# ProPrj__v1_0_2025-02-24.net
KiCad netlist of a schematic drawn in EasyEDA Pro
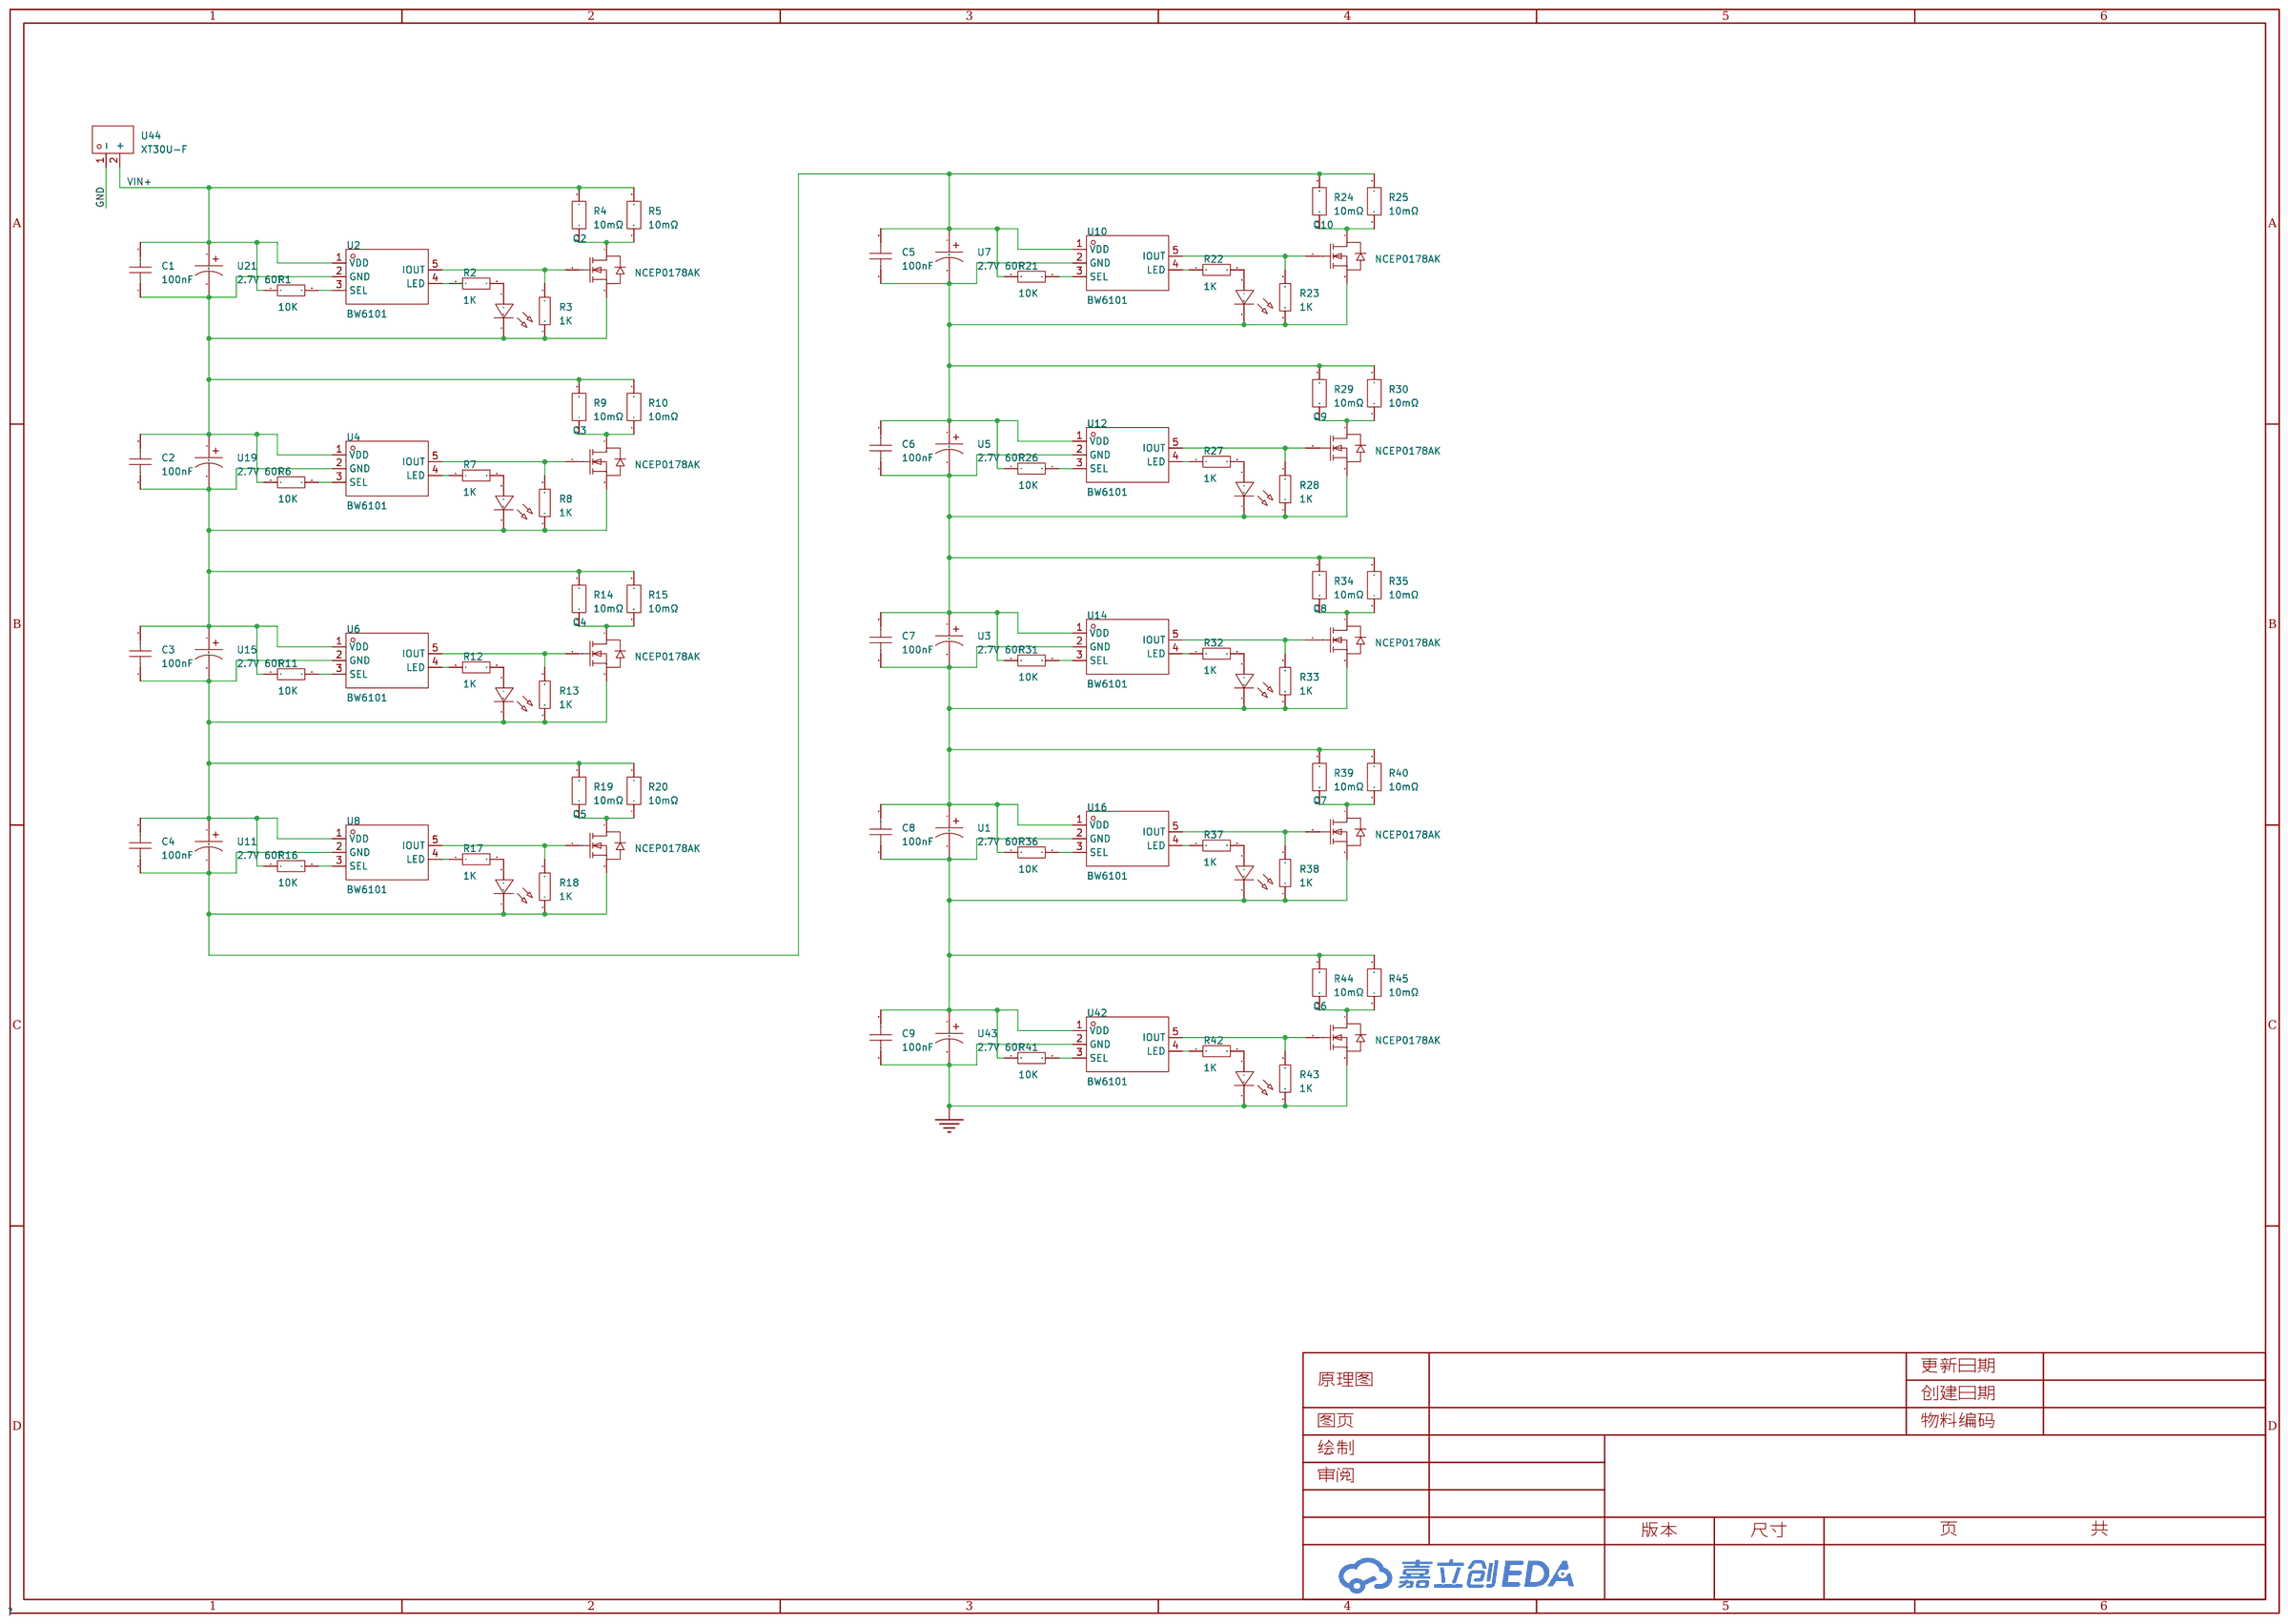
[diagram p0: schematic sheet]

(export (version "E")
  (design (tool "Eeschema 10.0.6"))
  (components
    (comp (ref "C1")
      (value "100nF")
      (footprint "easyedapro:C0805")
      (libsource (lib "easyedapro") (part "CapAcitance"))
    )
    (comp (ref "C2")
      (value "100nF")
      (footprint "easyedapro:C0805")
      (libsource (lib "easyedapro") (part "CapAcitance"))
    )
    (comp (ref "C3")
      (value "100nF")
      (footprint "easyedapro:C0805")
      (libsource (lib "easyedapro") (part "CapAcitance"))
    )
    (comp (ref "C4")
      (value "100nF")
      (footprint "easyedapro:C0805")
      (libsource (lib "easyedapro") (part "CapAcitance"))
    )
    (comp (ref "C5")
      (value "100nF")
      (footprint "easyedapro:C0805")
      (libsource (lib "easyedapro") (part "CapAcitance"))
    )
    (comp (ref "C6")
      (value "100nF")
      (footprint "easyedapro:C0805")
      (libsource (lib "easyedapro") (part "CapAcitance"))
    )
    (comp (ref "C7")
      (value "100nF")
      (footprint "easyedapro:C0805")
      (libsource (lib "easyedapro") (part "CapAcitance"))
    )
    (comp (ref "C8")
      (value "100nF")
      (footprint "easyedapro:C0805")
      (libsource (lib "easyedapro") (part "CapAcitance"))
    )
    (comp (ref "C9")
      (value "100nF")
      (footprint "easyedapro:C0805")
      (libsource (lib "easyedapro") (part "CapAcitance"))
    )
    (comp (ref "LED1")
      (value "~")
      (footprint "easyedapro:LED_0603")
      (libsource (lib "easyedapro") (part "LED_R"))
    )
    (comp (ref "LED2")
      (value "~")
      (footprint "easyedapro:LED_0603")
      (libsource (lib "easyedapro") (part "LED_R"))
    )
    (comp (ref "LED3")
      (value "~")
      (footprint "easyedapro:LED_0603")
      (libsource (lib "easyedapro") (part "LED_R"))
    )
    (comp (ref "LED4")
      (value "~")
      (footprint "easyedapro:LED_0603")
      (libsource (lib "easyedapro") (part "LED_R"))
    )
    (comp (ref "LED5")
      (value "~")
      (footprint "easyedapro:LED_0603")
      (libsource (lib "easyedapro") (part "LED_R"))
    )
    (comp (ref "LED6")
      (value "~")
      (footprint "easyedapro:LED_0603")
      (libsource (lib "easyedapro") (part "LED_R"))
    )
    (comp (ref "LED7")
      (value "~")
      (footprint "easyedapro:LED_0603")
      (libsource (lib "easyedapro") (part "LED_R"))
    )
    (comp (ref "LED8")
      (value "~")
      (footprint "easyedapro:LED_0603")
      (libsource (lib "easyedapro") (part "LED_R"))
    )
    (comp (ref "LED9")
      (value "~")
      (footprint "easyedapro:LED_0603")
      (libsource (lib "easyedapro") (part "LED_R"))
    )
    (comp (ref "Q2")
      (value "NCEP0178AK")
      (footprint "easyedapro:TO-252-2_L6.5-W6.1-P4.58-LS10.0-TL")
      (fields (field (name "Manufacturer") "NCE(无锡新洁能)"))
      (libsource (lib "easyedapro") (part "NCEP0178AK"))
    )
    (comp (ref "Q3")
      (value "NCEP0178AK")
      (footprint "easyedapro:TO-252-2_L6.5-W6.1-P4.58-LS10.0-TL")
      (fields (field (name "Manufacturer") "NCE(无锡新洁能)"))
      (libsource (lib "easyedapro") (part "NCEP0178AK"))
    )
    (comp (ref "Q4")
      (value "NCEP0178AK")
      (footprint "easyedapro:TO-252-2_L6.5-W6.1-P4.58-LS10.0-TL")
      (fields (field (name "Manufacturer") "NCE(无锡新洁能)"))
      (libsource (lib "easyedapro") (part "NCEP0178AK"))
    )
    (comp (ref "Q5")
      (value "NCEP0178AK")
      (footprint "easyedapro:TO-252-2_L6.5-W6.1-P4.58-LS10.0-TL")
      (fields (field (name "Manufacturer") "NCE(无锡新洁能)"))
      (libsource (lib "easyedapro") (part "NCEP0178AK"))
    )
    (comp (ref "Q6")
      (value "NCEP0178AK")
      (footprint "easyedapro:TO-252-2_L6.5-W6.1-P4.58-LS10.0-TL")
      (fields (field (name "Manufacturer") "NCE(无锡新洁能)"))
      (libsource (lib "easyedapro") (part "NCEP0178AK"))
    )
    (comp (ref "Q7")
      (value "NCEP0178AK")
      (footprint "easyedapro:TO-252-2_L6.5-W6.1-P4.58-LS10.0-TL")
      (fields (field (name "Manufacturer") "NCE(无锡新洁能)"))
      (libsource (lib "easyedapro") (part "NCEP0178AK"))
    )
    (comp (ref "Q8")
      (value "NCEP0178AK")
      (footprint "easyedapro:TO-252-2_L6.5-W6.1-P4.58-LS10.0-TL")
      (fields (field (name "Manufacturer") "NCE(无锡新洁能)"))
      (libsource (lib "easyedapro") (part "NCEP0178AK"))
    )
    (comp (ref "Q9")
      (value "NCEP0178AK")
      (footprint "easyedapro:TO-252-2_L6.5-W6.1-P4.58-LS10.0-TL")
      (fields (field (name "Manufacturer") "NCE(无锡新洁能)"))
      (libsource (lib "easyedapro") (part "NCEP0178AK"))
    )
    (comp (ref "Q10")
      (value "NCEP0178AK")
      (footprint "easyedapro:TO-252-2_L6.5-W6.1-P4.58-LS10.0-TL")
      (fields (field (name "Manufacturer") "NCE(无锡新洁能)"))
      (libsource (lib "easyedapro") (part "NCEP0178AK"))
    )
    (comp (ref "R1") (value "10K") (footprint "easyedapro:R0603") (libsource (lib "easyedapro") (part "电阻")))
    (comp (ref "R2") (value "1K") (footprint "easyedapro:R0603") (libsource (lib "easyedapro") (part "电阻")))
    (comp (ref "R3") (value "1K") (footprint "easyedapro:R0603") (libsource (lib "easyedapro") (part "电阻")))
    (comp (ref "R4")
      (value "10mΩ")
      (footprint "easyedapro:RES-SMD_L6.4-W3.2-R2512")
      (description "电阻类型:采样电阻;阻值:10mΩ;精度:±1%;功率:3W;安装方式:贴片;")
      (fields
        (field (name "Manufacturer Part") "HoJLR2512-3W-10mR-1%")
        (field (name "Manufacturer") "Milliohm(毫欧)")
      )
      (libsource (lib "easyedapro") (part "HOJLR2512-3W-10MR-1%"))
    )
    (comp (ref "R5")
      (value "10mΩ")
      (footprint "easyedapro:RES-SMD_L6.4-W3.2-R2512")
      (description "电阻类型:采样电阻;阻值:10mΩ;精度:±1%;功率:3W;安装方式:贴片;")
      (fields
        (field (name "Manufacturer Part") "HoJLR2512-3W-10mR-1%")
        (field (name "Manufacturer") "Milliohm(毫欧)")
      )
      (libsource (lib "easyedapro") (part "HOJLR2512-3W-10MR-1%"))
    )
    (comp (ref "R6") (value "10K") (footprint "easyedapro:R0603") (libsource (lib "easyedapro") (part "电阻")))
    (comp (ref "R7") (value "1K") (footprint "easyedapro:R0603") (libsource (lib "easyedapro") (part "电阻")))
    (comp (ref "R8") (value "1K") (footprint "easyedapro:R0603") (libsource (lib "easyedapro") (part "电阻")))
    (comp (ref "R9")
      (value "10mΩ")
      (footprint "easyedapro:RES-SMD_L6.4-W3.2-R2512")
      (description "电阻类型:采样电阻;阻值:10mΩ;精度:±1%;功率:3W;安装方式:贴片;")
      (fields
        (field (name "Manufacturer Part") "HoJLR2512-3W-10mR-1%")
        (field (name "Manufacturer") "Milliohm(毫欧)")
      )
      (libsource (lib "easyedapro") (part "HOJLR2512-3W-10MR-1%"))
    )
    (comp (ref "R10")
      (value "10mΩ")
      (footprint "easyedapro:RES-SMD_L6.4-W3.2-R2512")
      (description "电阻类型:采样电阻;阻值:10mΩ;精度:±1%;功率:3W;安装方式:贴片;")
      (fields
        (field (name "Manufacturer Part") "HoJLR2512-3W-10mR-1%")
        (field (name "Manufacturer") "Milliohm(毫欧)")
      )
      (libsource (lib "easyedapro") (part "HOJLR2512-3W-10MR-1%"))
    )
    (comp (ref "R11") (value "10K") (footprint "easyedapro:R0603") (libsource (lib "easyedapro") (part "电阻")))
    (comp (ref "R12") (value "1K") (footprint "easyedapro:R0603") (libsource (lib "easyedapro") (part "电阻")))
    (comp (ref "R13") (value "1K") (footprint "easyedapro:R0603") (libsource (lib "easyedapro") (part "电阻")))
    (comp (ref "R14")
      (value "10mΩ")
      (footprint "easyedapro:RES-SMD_L6.4-W3.2-R2512")
      (description "电阻类型:采样电阻;阻值:10mΩ;精度:±1%;功率:3W;安装方式:贴片;")
      (fields
        (field (name "Manufacturer Part") "HoJLR2512-3W-10mR-1%")
        (field (name "Manufacturer") "Milliohm(毫欧)")
      )
      (libsource (lib "easyedapro") (part "HOJLR2512-3W-10MR-1%"))
    )
    (comp (ref "R15")
      (value "10mΩ")
      (footprint "easyedapro:RES-SMD_L6.4-W3.2-R2512")
      (description "电阻类型:采样电阻;阻值:10mΩ;精度:±1%;功率:3W;安装方式:贴片;")
      (fields
        (field (name "Manufacturer Part") "HoJLR2512-3W-10mR-1%")
        (field (name "Manufacturer") "Milliohm(毫欧)")
      )
      (libsource (lib "easyedapro") (part "HOJLR2512-3W-10MR-1%"))
    )
    (comp (ref "R16") (value "10K") (footprint "easyedapro:R0603") (libsource (lib "easyedapro") (part "电阻")))
    (comp (ref "R17") (value "1K") (footprint "easyedapro:R0603") (libsource (lib "easyedapro") (part "电阻")))
    (comp (ref "R18") (value "1K") (footprint "easyedapro:R0603") (libsource (lib "easyedapro") (part "电阻")))
    (comp (ref "R19")
      (value "10mΩ")
      (footprint "easyedapro:RES-SMD_L6.4-W3.2-R2512")
      (description "电阻类型:采样电阻;阻值:10mΩ;精度:±1%;功率:3W;安装方式:贴片;")
      (fields
        (field (name "Manufacturer Part") "HoJLR2512-3W-10mR-1%")
        (field (name "Manufacturer") "Milliohm(毫欧)")
      )
      (libsource (lib "easyedapro") (part "HOJLR2512-3W-10MR-1%"))
    )
    (comp (ref "R20")
      (value "10mΩ")
      (footprint "easyedapro:RES-SMD_L6.4-W3.2-R2512")
      (description "电阻类型:采样电阻;阻值:10mΩ;精度:±1%;功率:3W;安装方式:贴片;")
      (fields
        (field (name "Manufacturer Part") "HoJLR2512-3W-10mR-1%")
        (field (name "Manufacturer") "Milliohm(毫欧)")
      )
      (libsource (lib "easyedapro") (part "HOJLR2512-3W-10MR-1%"))
    )
    (comp (ref "R21") (value "10K") (footprint "easyedapro:R0603") (libsource (lib "easyedapro") (part "电阻")))
    (comp (ref "R22") (value "1K") (footprint "easyedapro:R0603") (libsource (lib "easyedapro") (part "电阻")))
    (comp (ref "R23") (value "1K") (footprint "easyedapro:R0603") (libsource (lib "easyedapro") (part "电阻")))
    (comp (ref "R24")
      (value "10mΩ")
      (footprint "easyedapro:RES-SMD_L6.4-W3.2-R2512")
      (description "电阻类型:采样电阻;阻值:10mΩ;精度:±1%;功率:3W;安装方式:贴片;")
      (fields
        (field (name "Manufacturer Part") "HoJLR2512-3W-10mR-1%")
        (field (name "Manufacturer") "Milliohm(毫欧)")
      )
      (libsource (lib "easyedapro") (part "HOJLR2512-3W-10MR-1%"))
    )
    (comp (ref "R25")
      (value "10mΩ")
      (footprint "easyedapro:RES-SMD_L6.4-W3.2-R2512")
      (description "电阻类型:采样电阻;阻值:10mΩ;精度:±1%;功率:3W;安装方式:贴片;")
      (fields
        (field (name "Manufacturer Part") "HoJLR2512-3W-10mR-1%")
        (field (name "Manufacturer") "Milliohm(毫欧)")
      )
      (libsource (lib "easyedapro") (part "HOJLR2512-3W-10MR-1%"))
    )
    (comp (ref "R26") (value "10K") (footprint "easyedapro:R0603") (libsource (lib "easyedapro") (part "电阻")))
    (comp (ref "R27") (value "1K") (footprint "easyedapro:R0603") (libsource (lib "easyedapro") (part "电阻")))
    (comp (ref "R28") (value "1K") (footprint "easyedapro:R0603") (libsource (lib "easyedapro") (part "电阻")))
    (comp (ref "R29")
      (value "10mΩ")
      (footprint "easyedapro:RES-SMD_L6.4-W3.2-R2512")
      (description "电阻类型:采样电阻;阻值:10mΩ;精度:±1%;功率:3W;安装方式:贴片;")
      (fields
        (field (name "Manufacturer Part") "HoJLR2512-3W-10mR-1%")
        (field (name "Manufacturer") "Milliohm(毫欧)")
      )
      (libsource (lib "easyedapro") (part "HOJLR2512-3W-10MR-1%"))
    )
    (comp (ref "R30")
      (value "10mΩ")
      (footprint "easyedapro:RES-SMD_L6.4-W3.2-R2512")
      (description "电阻类型:采样电阻;阻值:10mΩ;精度:±1%;功率:3W;安装方式:贴片;")
      (fields
        (field (name "Manufacturer Part") "HoJLR2512-3W-10mR-1%")
        (field (name "Manufacturer") "Milliohm(毫欧)")
      )
      (libsource (lib "easyedapro") (part "HOJLR2512-3W-10MR-1%"))
    )
    (comp (ref "R31") (value "10K") (footprint "easyedapro:R0603") (libsource (lib "easyedapro") (part "电阻")))
    (comp (ref "R32") (value "1K") (footprint "easyedapro:R0603") (libsource (lib "easyedapro") (part "电阻")))
    (comp (ref "R33") (value "1K") (footprint "easyedapro:R0603") (libsource (lib "easyedapro") (part "电阻")))
    (comp (ref "R34")
      (value "10mΩ")
      (footprint "easyedapro:RES-SMD_L6.4-W3.2-R2512")
      (description "电阻类型:采样电阻;阻值:10mΩ;精度:±1%;功率:3W;安装方式:贴片;")
      (fields
        (field (name "Manufacturer Part") "HoJLR2512-3W-10mR-1%")
        (field (name "Manufacturer") "Milliohm(毫欧)")
      )
      (libsource (lib "easyedapro") (part "HOJLR2512-3W-10MR-1%"))
    )
    (comp (ref "R35")
      (value "10mΩ")
      (footprint "easyedapro:RES-SMD_L6.4-W3.2-R2512")
      (description "电阻类型:采样电阻;阻值:10mΩ;精度:±1%;功率:3W;安装方式:贴片;")
      (fields
        (field (name "Manufacturer Part") "HoJLR2512-3W-10mR-1%")
        (field (name "Manufacturer") "Milliohm(毫欧)")
      )
      (libsource (lib "easyedapro") (part "HOJLR2512-3W-10MR-1%"))
    )
    (comp (ref "R36") (value "10K") (footprint "easyedapro:R0603") (libsource (lib "easyedapro") (part "电阻")))
    (comp (ref "R37") (value "1K") (footprint "easyedapro:R0603") (libsource (lib "easyedapro") (part "电阻")))
    (comp (ref "R38") (value "1K") (footprint "easyedapro:R0603") (libsource (lib "easyedapro") (part "电阻")))
    (comp (ref "R39")
      (value "10mΩ")
      (footprint "easyedapro:RES-SMD_L6.4-W3.2-R2512")
      (description "电阻类型:采样电阻;阻值:10mΩ;精度:±1%;功率:3W;安装方式:贴片;")
      (fields
        (field (name "Manufacturer Part") "HoJLR2512-3W-10mR-1%")
        (field (name "Manufacturer") "Milliohm(毫欧)")
      )
      (libsource (lib "easyedapro") (part "HOJLR2512-3W-10MR-1%"))
    )
    (comp (ref "R40")
      (value "10mΩ")
      (footprint "easyedapro:RES-SMD_L6.4-W3.2-R2512")
      (description "电阻类型:采样电阻;阻值:10mΩ;精度:±1%;功率:3W;安装方式:贴片;")
      (fields
        (field (name "Manufacturer Part") "HoJLR2512-3W-10mR-1%")
        (field (name "Manufacturer") "Milliohm(毫欧)")
      )
      (libsource (lib "easyedapro") (part "HOJLR2512-3W-10MR-1%"))
    )
    (comp (ref "R41") (value "10K") (footprint "easyedapro:R0603") (libsource (lib "easyedapro") (part "电阻")))
    (comp (ref "R42") (value "1K") (footprint "easyedapro:R0603") (libsource (lib "easyedapro") (part "电阻")))
    (comp (ref "R43") (value "1K") (footprint "easyedapro:R0603") (libsource (lib "easyedapro") (part "电阻")))
    (comp (ref "R44")
      (value "10mΩ")
      (footprint "easyedapro:RES-SMD_L6.4-W3.2-R2512")
      (description "电阻类型:采样电阻;阻值:10mΩ;精度:±1%;功率:3W;安装方式:贴片;")
      (fields
        (field (name "Manufacturer Part") "HoJLR2512-3W-10mR-1%")
        (field (name "Manufacturer") "Milliohm(毫欧)")
      )
      (libsource (lib "easyedapro") (part "HOJLR2512-3W-10MR-1%"))
    )
    (comp (ref "R45")
      (value "10mΩ")
      (footprint "easyedapro:RES-SMD_L6.4-W3.2-R2512")
      (description "电阻类型:采样电阻;阻值:10mΩ;精度:±1%;功率:3W;安装方式:贴片;")
      (fields
        (field (name "Manufacturer Part") "HoJLR2512-3W-10mR-1%")
        (field (name "Manufacturer") "Milliohm(毫欧)")
      )
      (libsource (lib "easyedapro") (part "HOJLR2512-3W-10MR-1%"))
    )
    (comp (ref "U1")
      (value "2.7V 60F")
      (footprint "easyedapro:CAP-TH_BD18.0-P7.50-D0.8-FD")
      (description "容值:50F;精度:±20%;额定电压:2.7V;漏电流:110uA@72hrs;等效串联电阻:18mΩ@1kHz;")
      (fields
        (field (name "Manufacturer Part") "CXHP2R7506R-TWX-M0 2.7V50F")
        (field (name "Manufacturer") "CDA(智烽维)")
      )
      (libsource (lib "easyedapro") (part "CXHP2R7506R-TWX-M0 2.7V50F"))
    )
    (comp (ref "U2")
      (value "BW6101")
      (footprint "easyedapro:SOT-23-5_L2.9-W1.6-P0.95-LS2.8-BL")
      (libsource (lib "easyedapro") (part "BW6101"))
    )
    (comp (ref "U3")
      (value "2.7V 60F")
      (footprint "easyedapro:CAP-TH_BD18.0-P7.50-D0.8-FD")
      (description "容值:50F;精度:±20%;额定电压:2.7V;漏电流:110uA@72hrs;等效串联电阻:18mΩ@1kHz;")
      (fields
        (field (name "Manufacturer Part") "CXHP2R7506R-TWX-M0 2.7V50F")
        (field (name "Manufacturer") "CDA(智烽维)")
      )
      (libsource (lib "easyedapro") (part "CXHP2R7506R-TWX-M0 2.7V50F"))
    )
    (comp (ref "U4")
      (value "BW6101")
      (footprint "easyedapro:SOT-23-5_L2.9-W1.6-P0.95-LS2.8-BL")
      (libsource (lib "easyedapro") (part "BW6101"))
    )
    (comp (ref "U5")
      (value "2.7V 60F")
      (footprint "easyedapro:CAP-TH_BD18.0-P7.50-D0.8-FD")
      (description "容值:50F;精度:±20%;额定电压:2.7V;漏电流:110uA@72hrs;等效串联电阻:18mΩ@1kHz;")
      (fields
        (field (name "Manufacturer Part") "CXHP2R7506R-TWX-M0 2.7V50F")
        (field (name "Manufacturer") "CDA(智烽维)")
      )
      (libsource (lib "easyedapro") (part "CXHP2R7506R-TWX-M0 2.7V50F"))
    )
    (comp (ref "U6")
      (value "BW6101")
      (footprint "easyedapro:SOT-23-5_L2.9-W1.6-P0.95-LS2.8-BL")
      (libsource (lib "easyedapro") (part "BW6101"))
    )
    (comp (ref "U7")
      (value "2.7V 60F")
      (footprint "easyedapro:CAP-TH_BD18.0-P7.50-D0.8-FD")
      (description "容值:50F;精度:±20%;额定电压:2.7V;漏电流:110uA@72hrs;等效串联电阻:18mΩ@1kHz;")
      (fields
        (field (name "Manufacturer Part") "CXHP2R7506R-TWX-M0 2.7V50F")
        (field (name "Manufacturer") "CDA(智烽维)")
      )
      (libsource (lib "easyedapro") (part "CXHP2R7506R-TWX-M0 2.7V50F"))
    )
    (comp (ref "U8")
      (value "BW6101")
      (footprint "easyedapro:SOT-23-5_L2.9-W1.6-P0.95-LS2.8-BL")
      (libsource (lib "easyedapro") (part "BW6101"))
    )
    (comp (ref "U10")
      (value "BW6101")
      (footprint "easyedapro:SOT-23-5_L2.9-W1.6-P0.95-LS2.8-BL")
      (libsource (lib "easyedapro") (part "BW6101"))
    )
    (comp (ref "U11")
      (value "2.7V 60F")
      (footprint "easyedapro:CAP-TH_BD18.0-P7.50-D0.8-FD")
      (description "容值:50F;精度:±20%;额定电压:2.7V;漏电流:110uA@72hrs;等效串联电阻:18mΩ@1kHz;")
      (fields
        (field (name "Manufacturer Part") "CXHP2R7506R-TWX-M0 2.7V50F")
        (field (name "Manufacturer") "CDA(智烽维)")
      )
      (libsource (lib "easyedapro") (part "CXHP2R7506R-TWX-M0 2.7V50F"))
    )
    (comp (ref "U12")
      (value "BW6101")
      (footprint "easyedapro:SOT-23-5_L2.9-W1.6-P0.95-LS2.8-BL")
      (libsource (lib "easyedapro") (part "BW6101"))
    )
    (comp (ref "U14")
      (value "BW6101")
      (footprint "easyedapro:SOT-23-5_L2.9-W1.6-P0.95-LS2.8-BL")
      (libsource (lib "easyedapro") (part "BW6101"))
    )
    (comp (ref "U15")
      (value "2.7V 60F")
      (footprint "easyedapro:CAP-TH_BD18.0-P7.50-D0.8-FD")
      (description "容值:50F;精度:±20%;额定电压:2.7V;漏电流:110uA@72hrs;等效串联电阻:18mΩ@1kHz;")
      (fields
        (field (name "Manufacturer Part") "CXHP2R7506R-TWX-M0 2.7V50F")
        (field (name "Manufacturer") "CDA(智烽维)")
      )
      (libsource (lib "easyedapro") (part "CXHP2R7506R-TWX-M0 2.7V50F"))
    )
    (comp (ref "U16")
      (value "BW6101")
      (footprint "easyedapro:SOT-23-5_L2.9-W1.6-P0.95-LS2.8-BL")
      (libsource (lib "easyedapro") (part "BW6101"))
    )
    (comp (ref "U19")
      (value "2.7V 60F")
      (footprint "easyedapro:CAP-TH_BD18.0-P7.50-D0.8-FD")
      (description "容值:50F;精度:±20%;额定电压:2.7V;漏电流:110uA@72hrs;等效串联电阻:18mΩ@1kHz;")
      (fields
        (field (name "Manufacturer Part") "CXHP2R7506R-TWX-M0 2.7V50F")
        (field (name "Manufacturer") "CDA(智烽维)")
      )
      (libsource (lib "easyedapro") (part "CXHP2R7506R-TWX-M0 2.7V50F"))
    )
    (comp (ref "U21")
      (value "2.7V 60F")
      (footprint "easyedapro:CAP-TH_BD18.0-P7.50-D0.8-FD")
      (description "容值:50F;精度:±20%;额定电压:2.7V;漏电流:110uA@72hrs;等效串联电阻:18mΩ@1kHz;")
      (fields
        (field (name "Manufacturer Part") "CXHP2R7506R-TWX-M0 2.7V50F")
        (field (name "Manufacturer") "CDA(智烽维)")
      )
      (libsource (lib "easyedapro") (part "CXHP2R7506R-TWX-M0 2.7V50F"))
    )
    (comp (ref "U42")
      (value "BW6101")
      (footprint "easyedapro:SOT-23-5_L2.9-W1.6-P0.95-LS2.8-BL")
      (libsource (lib "easyedapro") (part "BW6101"))
    )
    (comp (ref "U43")
      (value "2.7V 60F")
      (footprint "easyedapro:CAP-TH_BD18.0-P7.50-D0.8-FD")
      (description "容值:50F;精度:±20%;额定电压:2.7V;漏电流:110uA@72hrs;等效串联电阻:18mΩ@1kHz;")
      (fields
        (field (name "Manufacturer Part") "CXHP2R7506R-TWX-M0 2.7V50F")
        (field (name "Manufacturer") "CDA(智烽维)")
      )
      (libsource (lib "easyedapro") (part "CXHP2R7506R-TWX-M0 2.7V50F"))
    )
    (comp (ref "U44")
      (value "XT30U-F")
      (footprint "easyedapro:CONN-TH_XT30U-F")
      (description "类别:-;类型1:-;")
      (fields (field (name "Manufacturer") "AMASS(艾迈斯)"))
      (libsource (lib "easyedapro") (part "XT30U-F"))
    )
  )
  (nets
    (net (code "1") (name "/VIN+") (class "Default")
      (node (ref "C1") (pin "2") (pinfunction "2_2") (pintype "input"))
      (node (ref "R1") (pin "1") (pinfunction "1_1") (pintype "input"))
      (node (ref "R4") (pin "2") (pinfunction "2_2") (pintype "unspecified"))
      (node (ref "R5") (pin "2") (pinfunction "2_2") (pintype "unspecified"))
      (node (ref "U2") (pin "1") (pinfunction "VDD_1") (pintype "input"))
      (node (ref "U21") (pin "1") (pinfunction "1_1") (pintype "unspecified"))
      (node (ref "U44") (pin "2") (pinfunction "+_2") (pintype "unspecified"))
    )
    (net (code "2") (name "GND") (class "Default")
      (node (ref "C9") (pin "1") (pinfunction "1_1") (pintype "input"))
      (node (ref "LED9") (pin "1") (pinfunction "C_1") (pintype "input"))
      (node (ref "Q6") (pin "3") (pinfunction "S_3") (pintype "unspecified"))
      (node (ref "R43") (pin "1") (pinfunction "1_1") (pintype "input"))
      (node (ref "U42") (pin "2") (pinfunction "GND_2") (pintype "input"))
      (node (ref "U43") (pin "2") (pinfunction "2_2") (pintype "unspecified"))
      (node (ref "U44") (pin "1") (pinfunction "-_1") (pintype "unspecified"))
    )
    (net (code "3") (name "Net-(LED1-A)") (class "Default")
      (node (ref "LED1") (pin "2") (pinfunction "A_2") (pintype "input"))
      (node (ref "R2") (pin "2") (pinfunction "2_2") (pintype "input"))
    )
    (net (code "4") (name "Net-(LED1-C)") (class "Default")
      (node (ref "C1") (pin "1") (pinfunction "1_1") (pintype "input"))
      (node (ref "C2") (pin "2") (pinfunction "2_2") (pintype "input"))
      (node (ref "LED1") (pin "1") (pinfunction "C_1") (pintype "input"))
      (node (ref "Q2") (pin "3") (pinfunction "S_3") (pintype "unspecified"))
      (node (ref "R10") (pin "2") (pinfunction "2_2") (pintype "unspecified"))
      (node (ref "R3") (pin "1") (pinfunction "1_1") (pintype "input"))
      (node (ref "R6") (pin "1") (pinfunction "1_1") (pintype "input"))
      (node (ref "R9") (pin "2") (pinfunction "2_2") (pintype "unspecified"))
      (node (ref "U19") (pin "1") (pinfunction "1_1") (pintype "unspecified"))
      (node (ref "U2") (pin "2") (pinfunction "GND_2") (pintype "input"))
      (node (ref "U21") (pin "2") (pinfunction "2_2") (pintype "unspecified"))
      (node (ref "U4") (pin "1") (pinfunction "VDD_1") (pintype "input"))
    )
    (net (code "5") (name "Net-(LED2-A)") (class "Default")
      (node (ref "LED2") (pin "2") (pinfunction "A_2") (pintype "input"))
      (node (ref "R7") (pin "2") (pinfunction "2_2") (pintype "input"))
    )
    (net (code "6") (name "Net-(LED2-C)") (class "Default")
      (node (ref "C2") (pin "1") (pinfunction "1_1") (pintype "input"))
      (node (ref "C3") (pin "2") (pinfunction "2_2") (pintype "input"))
      (node (ref "LED2") (pin "1") (pinfunction "C_1") (pintype "input"))
      (node (ref "Q3") (pin "3") (pinfunction "S_3") (pintype "unspecified"))
      (node (ref "R11") (pin "1") (pinfunction "1_1") (pintype "input"))
      (node (ref "R14") (pin "2") (pinfunction "2_2") (pintype "unspecified"))
      (node (ref "R15") (pin "2") (pinfunction "2_2") (pintype "unspecified"))
      (node (ref "R8") (pin "1") (pinfunction "1_1") (pintype "input"))
      (node (ref "U15") (pin "1") (pinfunction "1_1") (pintype "unspecified"))
      (node (ref "U19") (pin "2") (pinfunction "2_2") (pintype "unspecified"))
      (node (ref "U4") (pin "2") (pinfunction "GND_2") (pintype "input"))
      (node (ref "U6") (pin "1") (pinfunction "VDD_1") (pintype "input"))
    )
    (net (code "7") (name "Net-(LED3-A)") (class "Default")
      (node (ref "LED3") (pin "2") (pinfunction "A_2") (pintype "input"))
      (node (ref "R12") (pin "2") (pinfunction "2_2") (pintype "input"))
    )
    (net (code "8") (name "Net-(LED3-C)") (class "Default")
      (node (ref "C3") (pin "1") (pinfunction "1_1") (pintype "input"))
      (node (ref "C4") (pin "2") (pinfunction "2_2") (pintype "input"))
      (node (ref "LED3") (pin "1") (pinfunction "C_1") (pintype "input"))
      (node (ref "Q4") (pin "3") (pinfunction "S_3") (pintype "unspecified"))
      (node (ref "R13") (pin "1") (pinfunction "1_1") (pintype "input"))
      (node (ref "R16") (pin "1") (pinfunction "1_1") (pintype "input"))
      (node (ref "R19") (pin "2") (pinfunction "2_2") (pintype "unspecified"))
      (node (ref "R20") (pin "2") (pinfunction "2_2") (pintype "unspecified"))
      (node (ref "U11") (pin "1") (pinfunction "1_1") (pintype "unspecified"))
      (node (ref "U15") (pin "2") (pinfunction "2_2") (pintype "unspecified"))
      (node (ref "U6") (pin "2") (pinfunction "GND_2") (pintype "input"))
      (node (ref "U8") (pin "1") (pinfunction "VDD_1") (pintype "input"))
    )
    (net (code "9") (name "Net-(LED4-A)") (class "Default")
      (node (ref "LED4") (pin "2") (pinfunction "A_2") (pintype "input"))
      (node (ref "R17") (pin "2") (pinfunction "2_2") (pintype "input"))
    )
    (net (code "10") (name "Net-(LED4-C)") (class "Default")
      (node (ref "C4") (pin "1") (pinfunction "1_1") (pintype "input"))
      (node (ref "C5") (pin "2") (pinfunction "2_2") (pintype "input"))
      (node (ref "LED4") (pin "1") (pinfunction "C_1") (pintype "input"))
      (node (ref "Q5") (pin "3") (pinfunction "S_3") (pintype "unspecified"))
      (node (ref "R18") (pin "1") (pinfunction "1_1") (pintype "input"))
      (node (ref "R21") (pin "1") (pinfunction "1_1") (pintype "input"))
      (node (ref "R24") (pin "2") (pinfunction "2_2") (pintype "unspecified"))
      (node (ref "R25") (pin "2") (pinfunction "2_2") (pintype "unspecified"))
      (node (ref "U10") (pin "1") (pinfunction "VDD_1") (pintype "input"))
      (node (ref "U11") (pin "2") (pinfunction "2_2") (pintype "unspecified"))
      (node (ref "U7") (pin "1") (pinfunction "1_1") (pintype "unspecified"))
      (node (ref "U8") (pin "2") (pinfunction "GND_2") (pintype "input"))
    )
    (net (code "11") (name "Net-(LED5-A)") (class "Default")
      (node (ref "LED5") (pin "2") (pinfunction "A_2") (pintype "input"))
      (node (ref "R22") (pin "2") (pinfunction "2_2") (pintype "input"))
    )
    (net (code "12") (name "Net-(LED5-C)") (class "Default")
      (node (ref "C5") (pin "1") (pinfunction "1_1") (pintype "input"))
      (node (ref "C6") (pin "2") (pinfunction "2_2") (pintype "input"))
      (node (ref "LED5") (pin "1") (pinfunction "C_1") (pintype "input"))
      (node (ref "Q10") (pin "3") (pinfunction "S_3") (pintype "unspecified"))
      (node (ref "R23") (pin "1") (pinfunction "1_1") (pintype "input"))
      (node (ref "R26") (pin "1") (pinfunction "1_1") (pintype "input"))
      (node (ref "R29") (pin "2") (pinfunction "2_2") (pintype "unspecified"))
      (node (ref "R30") (pin "2") (pinfunction "2_2") (pintype "unspecified"))
      (node (ref "U10") (pin "2") (pinfunction "GND_2") (pintype "input"))
      (node (ref "U12") (pin "1") (pinfunction "VDD_1") (pintype "input"))
      (node (ref "U5") (pin "1") (pinfunction "1_1") (pintype "unspecified"))
      (node (ref "U7") (pin "2") (pinfunction "2_2") (pintype "unspecified"))
    )
    (net (code "13") (name "Net-(LED6-A)") (class "Default")
      (node (ref "LED6") (pin "2") (pinfunction "A_2") (pintype "input"))
      (node (ref "R27") (pin "2") (pinfunction "2_2") (pintype "input"))
    )
    (net (code "14") (name "Net-(LED6-C)") (class "Default")
      (node (ref "C6") (pin "1") (pinfunction "1_1") (pintype "input"))
      (node (ref "C7") (pin "2") (pinfunction "2_2") (pintype "input"))
      (node (ref "LED6") (pin "1") (pinfunction "C_1") (pintype "input"))
      (node (ref "Q9") (pin "3") (pinfunction "S_3") (pintype "unspecified"))
      (node (ref "R28") (pin "1") (pinfunction "1_1") (pintype "input"))
      (node (ref "R31") (pin "1") (pinfunction "1_1") (pintype "input"))
      (node (ref "R34") (pin "2") (pinfunction "2_2") (pintype "unspecified"))
      (node (ref "R35") (pin "2") (pinfunction "2_2") (pintype "unspecified"))
      (node (ref "U12") (pin "2") (pinfunction "GND_2") (pintype "input"))
      (node (ref "U14") (pin "1") (pinfunction "VDD_1") (pintype "input"))
      (node (ref "U3") (pin "1") (pinfunction "1_1") (pintype "unspecified"))
      (node (ref "U5") (pin "2") (pinfunction "2_2") (pintype "unspecified"))
    )
    (net (code "15") (name "Net-(LED7-A)") (class "Default")
      (node (ref "LED7") (pin "2") (pinfunction "A_2") (pintype "input"))
      (node (ref "R32") (pin "2") (pinfunction "2_2") (pintype "input"))
    )
    (net (code "16") (name "Net-(LED7-C)") (class "Default")
      (node (ref "C7") (pin "1") (pinfunction "1_1") (pintype "input"))
      (node (ref "C8") (pin "2") (pinfunction "2_2") (pintype "input"))
      (node (ref "LED7") (pin "1") (pinfunction "C_1") (pintype "input"))
      (node (ref "Q8") (pin "3") (pinfunction "S_3") (pintype "unspecified"))
      (node (ref "R33") (pin "1") (pinfunction "1_1") (pintype "input"))
      (node (ref "R36") (pin "1") (pinfunction "1_1") (pintype "input"))
      (node (ref "R39") (pin "2") (pinfunction "2_2") (pintype "unspecified"))
      (node (ref "R40") (pin "2") (pinfunction "2_2") (pintype "unspecified"))
      (node (ref "U1") (pin "1") (pinfunction "1_1") (pintype "unspecified"))
      (node (ref "U14") (pin "2") (pinfunction "GND_2") (pintype "input"))
      (node (ref "U16") (pin "1") (pinfunction "VDD_1") (pintype "input"))
      (node (ref "U3") (pin "2") (pinfunction "2_2") (pintype "unspecified"))
    )
    (net (code "17") (name "Net-(LED8-A)") (class "Default")
      (node (ref "LED8") (pin "2") (pinfunction "A_2") (pintype "input"))
      (node (ref "R37") (pin "2") (pinfunction "2_2") (pintype "input"))
    )
    (net (code "18") (name "Net-(LED8-C)") (class "Default")
      (node (ref "C8") (pin "1") (pinfunction "1_1") (pintype "input"))
      (node (ref "C9") (pin "2") (pinfunction "2_2") (pintype "input"))
      (node (ref "LED8") (pin "1") (pinfunction "C_1") (pintype "input"))
      (node (ref "Q7") (pin "3") (pinfunction "S_3") (pintype "unspecified"))
      (node (ref "R38") (pin "1") (pinfunction "1_1") (pintype "input"))
      (node (ref "R41") (pin "1") (pinfunction "1_1") (pintype "input"))
      (node (ref "R44") (pin "2") (pinfunction "2_2") (pintype "unspecified"))
      (node (ref "R45") (pin "2") (pinfunction "2_2") (pintype "unspecified"))
      (node (ref "U1") (pin "2") (pinfunction "2_2") (pintype "unspecified"))
      (node (ref "U16") (pin "2") (pinfunction "GND_2") (pintype "input"))
      (node (ref "U42") (pin "1") (pinfunction "VDD_1") (pintype "input"))
      (node (ref "U43") (pin "1") (pinfunction "1_1") (pintype "unspecified"))
    )
    (net (code "19") (name "Net-(LED9-A)") (class "Default")
      (node (ref "LED9") (pin "2") (pinfunction "A_2") (pintype "input"))
      (node (ref "R42") (pin "2") (pinfunction "2_2") (pintype "input"))
    )
    (net (code "20") (name "Net-(Q2-D)") (class "Default")
      (node (ref "Q2") (pin "4") (pinfunction "D_4") (pintype "unspecified"))
      (node (ref "R4") (pin "1") (pinfunction "1_1") (pintype "unspecified"))
      (node (ref "R5") (pin "1") (pinfunction "1_1") (pintype "unspecified"))
    )
    (net (code "21") (name "Net-(Q2-G)") (class "Default")
      (node (ref "Q2") (pin "1") (pinfunction "G_1") (pintype "unspecified"))
      (node (ref "R3") (pin "2") (pinfunction "2_2") (pintype "input"))
      (node (ref "U2") (pin "5") (pinfunction "IOUT_5") (pintype "input"))
    )
    (net (code "22") (name "Net-(Q3-D)") (class "Default")
      (node (ref "Q3") (pin "4") (pinfunction "D_4") (pintype "unspecified"))
      (node (ref "R10") (pin "1") (pinfunction "1_1") (pintype "unspecified"))
      (node (ref "R9") (pin "1") (pinfunction "1_1") (pintype "unspecified"))
    )
    (net (code "23") (name "Net-(Q3-G)") (class "Default")
      (node (ref "Q3") (pin "1") (pinfunction "G_1") (pintype "unspecified"))
      (node (ref "R8") (pin "2") (pinfunction "2_2") (pintype "input"))
      (node (ref "U4") (pin "5") (pinfunction "IOUT_5") (pintype "input"))
    )
    (net (code "24") (name "Net-(Q4-D)") (class "Default")
      (node (ref "Q4") (pin "4") (pinfunction "D_4") (pintype "unspecified"))
      (node (ref "R14") (pin "1") (pinfunction "1_1") (pintype "unspecified"))
      (node (ref "R15") (pin "1") (pinfunction "1_1") (pintype "unspecified"))
    )
    (net (code "25") (name "Net-(Q4-G)") (class "Default")
      (node (ref "Q4") (pin "1") (pinfunction "G_1") (pintype "unspecified"))
      (node (ref "R13") (pin "2") (pinfunction "2_2") (pintype "input"))
      (node (ref "U6") (pin "5") (pinfunction "IOUT_5") (pintype "input"))
    )
    (net (code "26") (name "Net-(Q5-D)") (class "Default")
      (node (ref "Q5") (pin "4") (pinfunction "D_4") (pintype "unspecified"))
      (node (ref "R19") (pin "1") (pinfunction "1_1") (pintype "unspecified"))
      (node (ref "R20") (pin "1") (pinfunction "1_1") (pintype "unspecified"))
    )
    (net (code "27") (name "Net-(Q5-G)") (class "Default")
      (node (ref "Q5") (pin "1") (pinfunction "G_1") (pintype "unspecified"))
      (node (ref "R18") (pin "2") (pinfunction "2_2") (pintype "input"))
      (node (ref "U8") (pin "5") (pinfunction "IOUT_5") (pintype "input"))
    )
    (net (code "28") (name "Net-(Q6-D)") (class "Default")
      (node (ref "Q6") (pin "4") (pinfunction "D_4") (pintype "unspecified"))
      (node (ref "R44") (pin "1") (pinfunction "1_1") (pintype "unspecified"))
      (node (ref "R45") (pin "1") (pinfunction "1_1") (pintype "unspecified"))
    )
    (net (code "29") (name "Net-(Q6-G)") (class "Default")
      (node (ref "Q6") (pin "1") (pinfunction "G_1") (pintype "unspecified"))
      (node (ref "R43") (pin "2") (pinfunction "2_2") (pintype "input"))
      (node (ref "U42") (pin "5") (pinfunction "IOUT_5") (pintype "input"))
    )
    (net (code "30") (name "Net-(Q7-D)") (class "Default")
      (node (ref "Q7") (pin "4") (pinfunction "D_4") (pintype "unspecified"))
      (node (ref "R39") (pin "1") (pinfunction "1_1") (pintype "unspecified"))
      (node (ref "R40") (pin "1") (pinfunction "1_1") (pintype "unspecified"))
    )
    (net (code "31") (name "Net-(Q7-G)") (class "Default")
      (node (ref "Q7") (pin "1") (pinfunction "G_1") (pintype "unspecified"))
      (node (ref "R38") (pin "2") (pinfunction "2_2") (pintype "input"))
      (node (ref "U16") (pin "5") (pinfunction "IOUT_5") (pintype "input"))
    )
    (net (code "32") (name "Net-(Q8-D)") (class "Default")
      (node (ref "Q8") (pin "4") (pinfunction "D_4") (pintype "unspecified"))
      (node (ref "R34") (pin "1") (pinfunction "1_1") (pintype "unspecified"))
      (node (ref "R35") (pin "1") (pinfunction "1_1") (pintype "unspecified"))
    )
    (net (code "33") (name "Net-(Q8-G)") (class "Default")
      (node (ref "Q8") (pin "1") (pinfunction "G_1") (pintype "unspecified"))
      (node (ref "R33") (pin "2") (pinfunction "2_2") (pintype "input"))
      (node (ref "U14") (pin "5") (pinfunction "IOUT_5") (pintype "input"))
    )
    (net (code "34") (name "Net-(Q9-D)") (class "Default")
      (node (ref "Q9") (pin "4") (pinfunction "D_4") (pintype "unspecified"))
      (node (ref "R29") (pin "1") (pinfunction "1_1") (pintype "unspecified"))
      (node (ref "R30") (pin "1") (pinfunction "1_1") (pintype "unspecified"))
    )
    (net (code "35") (name "Net-(Q9-G)") (class "Default")
      (node (ref "Q9") (pin "1") (pinfunction "G_1") (pintype "unspecified"))
      (node (ref "R28") (pin "2") (pinfunction "2_2") (pintype "input"))
      (node (ref "U12") (pin "5") (pinfunction "IOUT_5") (pintype "input"))
    )
    (net (code "36") (name "Net-(Q10-D)") (class "Default")
      (node (ref "Q10") (pin "4") (pinfunction "D_4") (pintype "unspecified"))
      (node (ref "R24") (pin "1") (pinfunction "1_1") (pintype "unspecified"))
      (node (ref "R25") (pin "1") (pinfunction "1_1") (pintype "unspecified"))
    )
    (net (code "37") (name "Net-(Q10-G)") (class "Default")
      (node (ref "Q10") (pin "1") (pinfunction "G_1") (pintype "unspecified"))
      (node (ref "R23") (pin "2") (pinfunction "2_2") (pintype "input"))
      (node (ref "U10") (pin "5") (pinfunction "IOUT_5") (pintype "input"))
    )
    (net (code "38") (name "Net-(U2-LED)") (class "Default")
      (node (ref "R2") (pin "1") (pinfunction "1_1") (pintype "input"))
      (node (ref "U2") (pin "4") (pinfunction "LED_4") (pintype "input"))
    )
    (net (code "39") (name "Net-(U2-SEL)") (class "Default")
      (node (ref "R1") (pin "2") (pinfunction "2_2") (pintype "input"))
      (node (ref "U2") (pin "3") (pinfunction "SEL_3") (pintype "input"))
    )
    (net (code "40") (name "Net-(U4-LED)") (class "Default")
      (node (ref "R7") (pin "1") (pinfunction "1_1") (pintype "input"))
      (node (ref "U4") (pin "4") (pinfunction "LED_4") (pintype "input"))
    )
    (net (code "41") (name "Net-(U4-SEL)") (class "Default")
      (node (ref "R6") (pin "2") (pinfunction "2_2") (pintype "input"))
      (node (ref "U4") (pin "3") (pinfunction "SEL_3") (pintype "input"))
    )
    (net (code "42") (name "Net-(U6-LED)") (class "Default")
      (node (ref "R12") (pin "1") (pinfunction "1_1") (pintype "input"))
      (node (ref "U6") (pin "4") (pinfunction "LED_4") (pintype "input"))
    )
    (net (code "43") (name "Net-(U6-SEL)") (class "Default")
      (node (ref "R11") (pin "2") (pinfunction "2_2") (pintype "input"))
      (node (ref "U6") (pin "3") (pinfunction "SEL_3") (pintype "input"))
    )
    (net (code "44") (name "Net-(U8-LED)") (class "Default")
      (node (ref "R17") (pin "1") (pinfunction "1_1") (pintype "input"))
      (node (ref "U8") (pin "4") (pinfunction "LED_4") (pintype "input"))
    )
    (net (code "45") (name "Net-(U8-SEL)") (class "Default")
      (node (ref "R16") (pin "2") (pinfunction "2_2") (pintype "input"))
      (node (ref "U8") (pin "3") (pinfunction "SEL_3") (pintype "input"))
    )
    (net (code "46") (name "Net-(U10-LED)") (class "Default")
      (node (ref "R22") (pin "1") (pinfunction "1_1") (pintype "input"))
      (node (ref "U10") (pin "4") (pinfunction "LED_4") (pintype "input"))
    )
    (net (code "47") (name "Net-(U10-SEL)") (class "Default")
      (node (ref "R21") (pin "2") (pinfunction "2_2") (pintype "input"))
      (node (ref "U10") (pin "3") (pinfunction "SEL_3") (pintype "input"))
    )
    (net (code "48") (name "Net-(U12-LED)") (class "Default")
      (node (ref "R27") (pin "1") (pinfunction "1_1") (pintype "input"))
      (node (ref "U12") (pin "4") (pinfunction "LED_4") (pintype "input"))
    )
    (net (code "49") (name "Net-(U12-SEL)") (class "Default")
      (node (ref "R26") (pin "2") (pinfunction "2_2") (pintype "input"))
      (node (ref "U12") (pin "3") (pinfunction "SEL_3") (pintype "input"))
    )
    (net (code "50") (name "Net-(U14-LED)") (class "Default")
      (node (ref "R32") (pin "1") (pinfunction "1_1") (pintype "input"))
      (node (ref "U14") (pin "4") (pinfunction "LED_4") (pintype "input"))
    )
    (net (code "51") (name "Net-(U14-SEL)") (class "Default")
      (node (ref "R31") (pin "2") (pinfunction "2_2") (pintype "input"))
      (node (ref "U14") (pin "3") (pinfunction "SEL_3") (pintype "input"))
    )
    (net (code "52") (name "Net-(U16-LED)") (class "Default")
      (node (ref "R37") (pin "1") (pinfunction "1_1") (pintype "input"))
      (node (ref "U16") (pin "4") (pinfunction "LED_4") (pintype "input"))
    )
    (net (code "53") (name "Net-(U16-SEL)") (class "Default")
      (node (ref "R36") (pin "2") (pinfunction "2_2") (pintype "input"))
      (node (ref "U16") (pin "3") (pinfunction "SEL_3") (pintype "input"))
    )
    (net (code "54") (name "Net-(U42-LED)") (class "Default")
      (node (ref "R42") (pin "1") (pinfunction "1_1") (pintype "input"))
      (node (ref "U42") (pin "4") (pinfunction "LED_4") (pintype "input"))
    )
    (net (code "55") (name "Net-(U42-SEL)") (class "Default")
      (node (ref "R41") (pin "2") (pinfunction "2_2") (pintype "input"))
      (node (ref "U42") (pin "3") (pinfunction "SEL_3") (pintype "input"))
    )
  )
)
